# programmer.net
KiCad netlist of a schematic drawn in EAGLE
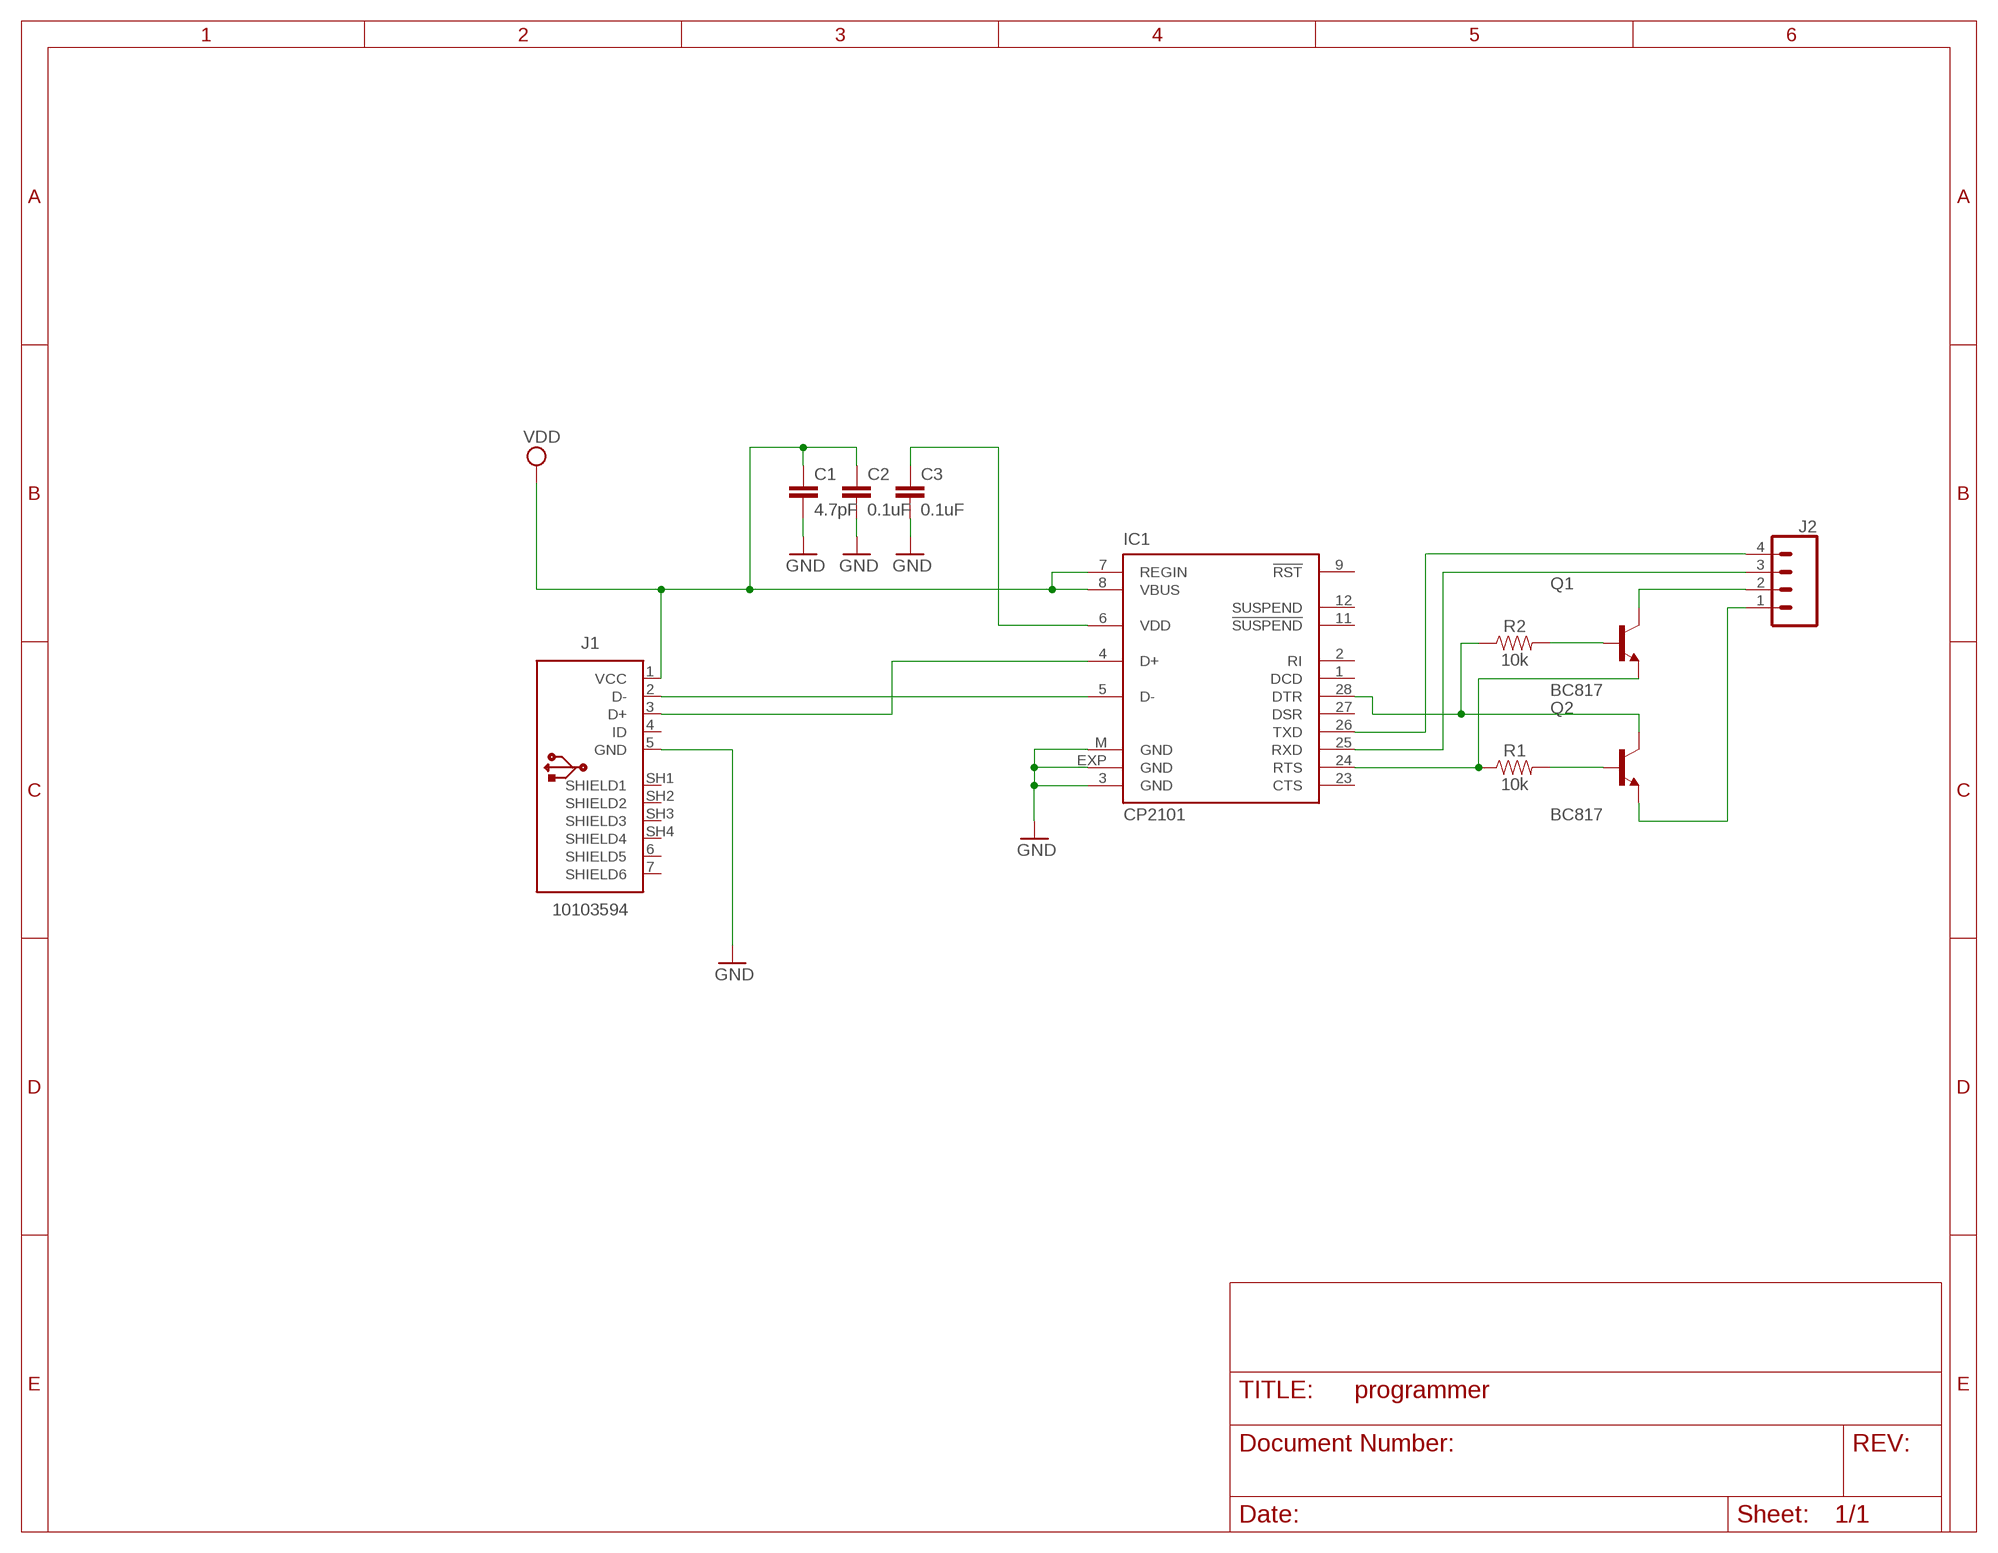
[diagram p0: schematic, sheet 1]

(export (version "E")
  (design (tool "Eeschema 10.0.6"))
  (components
    (comp (ref "C1")
      (value "4.7pF")
      (footprint "eagle-import:0603")
      (libsource (lib "eagle-import") (part "4.7PF-0603-50V-5%"))
    )
    (comp (ref "C2")
      (value "0.1uF")
      (footprint "eagle-import:0402")
      (libsource (lib "eagle-import") (part "0.1UF-0402-16V-10%"))
    )
    (comp (ref "C3")
      (value "0.1uF")
      (footprint "eagle-import:0402")
      (libsource (lib "eagle-import") (part "0.1UF-0402-16V-10%"))
    )
    (comp (ref "IC1")
      (value "CP2101")
      (footprint "eagle-import:MLP28")
      (fields (field (name "MF") "FARNELL") (field (name "MPN") "CP2102-GM"))
      (libsource (lib "eagle-import") (part "CP2101"))
    )
    (comp (ref "J1")
      (value "10103594")
      (footprint "eagle-import:10103594")
      (fields (field (name "MANUFACTURER") "Amphenol ICC (FCI)") (field (name "MPN") "10103594-0001LF"))
      (libsource (lib "eagle-import") (part "10103594"))
    )
    (comp (ref "J2")
      (value "CONN_04")
      (footprint "eagle-import:1X04")
      (libsource (lib "eagle-import") (part "CONN_04"))
    )
    (comp (ref "Q1")
      (value "BC817")
      (footprint "eagle-import:SOT95P230X110-3N")
      (fields (field (name "MF") "Rectron"))
      (libsource (lib "eagle-import") (part "BC817"))
    )
    (comp (ref "Q2")
      (value "BC817")
      (footprint "eagle-import:SOT95P230X110-3N")
      (fields (field (name "MF") "Rectron"))
      (libsource (lib "eagle-import") (part "BC817"))
    )
    (comp (ref "R1")
      (value "10k")
      (footprint "eagle-import:AXIAL-0.3")
      (libsource (lib "eagle-import") (part "10KOHM-HORIZ-1/4W-1%"))
    )
    (comp (ref "R2")
      (value "10k")
      (footprint "eagle-import:AXIAL-0.3")
      (libsource (lib "eagle-import") (part "10KOHM-HORIZ-1/4W-1%"))
    )
  )
  (nets
    (net (code "1") (name "/SHIELD1") (class "Default")
      (node (ref "J1") (pin "SH1") (pinfunction "SHIELD1_SH1") (pintype "power_in"))
    )
    (net (code "2") (name "/SHIELD2") (class "Default")
      (node (ref "J1") (pin "SH2") (pinfunction "SHIELD2_SH2") (pintype "power_in"))
    )
    (net (code "3") (name "/SHIELD3") (class "Default")
      (node (ref "J1") (pin "SH3") (pinfunction "SHIELD3_SH3") (pintype "power_in"))
    )
    (net (code "4") (name "/SHIELD4") (class "Default")
      (node (ref "J1") (pin "SH4") (pinfunction "SHIELD4_SH4") (pintype "power_in"))
    )
    (net (code "5") (name "/SHIELD5") (class "Default")
      (node (ref "J1") (pin "6") (pinfunction "SHIELD5_6") (pintype "power_in"))
    )
    (net (code "6") (name "/SHIELD6") (class "Default")
      (node (ref "J1") (pin "7") (pinfunction "SHIELD6_7") (pintype "power_in"))
    )
    (net (code "7") (name "GND") (class "Default")
      (node (ref "C1") (pin "2") (pinfunction "2_2") (pintype "passive"))
      (node (ref "C2") (pin "2") (pinfunction "2_2") (pintype "passive"))
      (node (ref "C3") (pin "2") (pinfunction "2_2") (pintype "passive"))
      (node (ref "IC1") (pin "3") (pinfunction "GND_3") (pintype "power_in"))
      (node (ref "IC1") (pin "EXP") (pinfunction "GND_EXP") (pintype "power_in"))
      (node (ref "IC1") (pin "M") (pinfunction "GND_M") (pintype "power_in"))
      (node (ref "J1") (pin "5") (pinfunction "GND_5") (pintype "power_in"))
    )
    (net (code "8") (name "Net-(IC1-D+)") (class "Default")
      (node (ref "IC1") (pin "4") (pinfunction "D+_4") (pintype "bidirectional"))
      (node (ref "J1") (pin "3") (pinfunction "D+_3") (pintype "bidirectional"))
    )
    (net (code "9") (name "Net-(IC1-D-)") (class "Default")
      (node (ref "IC1") (pin "5") (pinfunction "D-_5") (pintype "bidirectional"))
      (node (ref "J1") (pin "2") (pinfunction "D-_2") (pintype "bidirectional"))
    )
    (net (code "10") (name "Net-(IC1-DTR)") (class "Default")
      (node (ref "IC1") (pin "28") (pinfunction "DTR_28") (pintype "output"))
      (node (ref "Q2") (pin "3") (pinfunction "C_3") (pintype "passive"))
      (node (ref "R2") (pin "P$1") (pinfunction "1_P$1") (pintype "passive"))
    )
    (net (code "11") (name "Net-(IC1-RTS)") (class "Default")
      (node (ref "IC1") (pin "24") (pinfunction "RTS_24") (pintype "output"))
      (node (ref "Q1") (pin "2") (pinfunction "E_2") (pintype "passive"))
      (node (ref "R1") (pin "P$1") (pinfunction "1_P$1") (pintype "passive"))
    )
    (net (code "12") (name "Net-(IC1-RXD)") (class "Default")
      (node (ref "IC1") (pin "25") (pinfunction "RXD_25") (pintype "input"))
      (node (ref "J2") (pin "3") (pinfunction "3_3") (pintype "passive"))
    )
    (net (code "13") (name "Net-(IC1-TXD)") (class "Default")
      (node (ref "IC1") (pin "26") (pinfunction "TXD_26") (pintype "output"))
      (node (ref "J2") (pin "4") (pinfunction "4_4") (pintype "passive"))
    )
    (net (code "14") (name "Net-(IC1-VDD)") (class "Default")
      (node (ref "C3") (pin "1") (pinfunction "1_1") (pintype "passive"))
      (node (ref "IC1") (pin "6") (pinfunction "VDD_6") (pintype "power_in"))
    )
    (net (code "15") (name "Net-(Q1-B)") (class "Default")
      (node (ref "Q1") (pin "1") (pinfunction "B_1") (pintype "passive"))
      (node (ref "R2") (pin "P$2") (pinfunction "2_P$2") (pintype "passive"))
    )
    (net (code "16") (name "Net-(Q1-C)") (class "Default")
      (node (ref "J2") (pin "2") (pinfunction "2_2") (pintype "passive"))
      (node (ref "Q1") (pin "3") (pinfunction "C_3") (pintype "passive"))
    )
    (net (code "17") (name "Net-(Q2-B)") (class "Default")
      (node (ref "Q2") (pin "1") (pinfunction "B_1") (pintype "passive"))
      (node (ref "R1") (pin "P$2") (pinfunction "2_P$2") (pintype "passive"))
    )
    (net (code "18") (name "Net-(Q2-E)") (class "Default")
      (node (ref "J2") (pin "1") (pinfunction "1_1") (pintype "passive"))
      (node (ref "Q2") (pin "2") (pinfunction "E_2") (pintype "passive"))
    )
    (net (code "19") (name "VDD") (class "Default")
      (node (ref "C1") (pin "1") (pinfunction "1_1") (pintype "passive"))
      (node (ref "C2") (pin "1") (pinfunction "1_1") (pintype "passive"))
      (node (ref "IC1") (pin "7") (pinfunction "REGIN_7") (pintype "passive"))
      (node (ref "IC1") (pin "8") (pinfunction "VBUS_8") (pintype "input"))
      (node (ref "J1") (pin "1") (pinfunction "VCC_1") (pintype "power_in"))
    )
    (net (code "20") (name "unconnected-(IC1-CTS-Pad23)") (class "Default")
      (node (ref "IC1") (pin "23") (pinfunction "CTS_23") (pintype "input"))
    )
    (net (code "21") (name "unconnected-(IC1-DCD-Pad1)") (class "Default")
      (node (ref "IC1") (pin "1") (pinfunction "DCD_1") (pintype "input"))
    )
    (net (code "22") (name "unconnected-(IC1-DSR-Pad27)") (class "Default")
      (node (ref "IC1") (pin "27") (pinfunction "DSR_27") (pintype "input"))
    )
    (net (code "23") (name "unconnected-(IC1-RI-Pad2)") (class "Default")
      (node (ref "IC1") (pin "2") (pinfunction "RI_2") (pintype "input"))
    )
    (net (code "24") (name "unconnected-(IC1-SUSPEND-Pad12)") (class "Default")
      (node (ref "IC1") (pin "12") (pinfunction "SUSPEND_12") (pintype "output"))
    )
    (net (code "25") (name "unconnected-(IC1-~{RST}-Pad9)") (class "Default")
      (node (ref "IC1") (pin "9") (pinfunction "~{RST}_9") (pintype "bidirectional"))
    )
    (net (code "26") (name "unconnected-(IC1-~{SUSPEND}-Pad11)") (class "Default")
      (node (ref "IC1") (pin "11") (pinfunction "~{SUSPEND}_11") (pintype "output"))
    )
    (net (code "27") (name "unconnected-(J1-ID-Pad4)") (class "Default")
      (node (ref "J1") (pin "4") (pinfunction "ID_4") (pintype "bidirectional"))
    )
  )
)
